# Master_System_Converter_Plus.net
KiCad netlist of a schematic drawn in EasyEDA
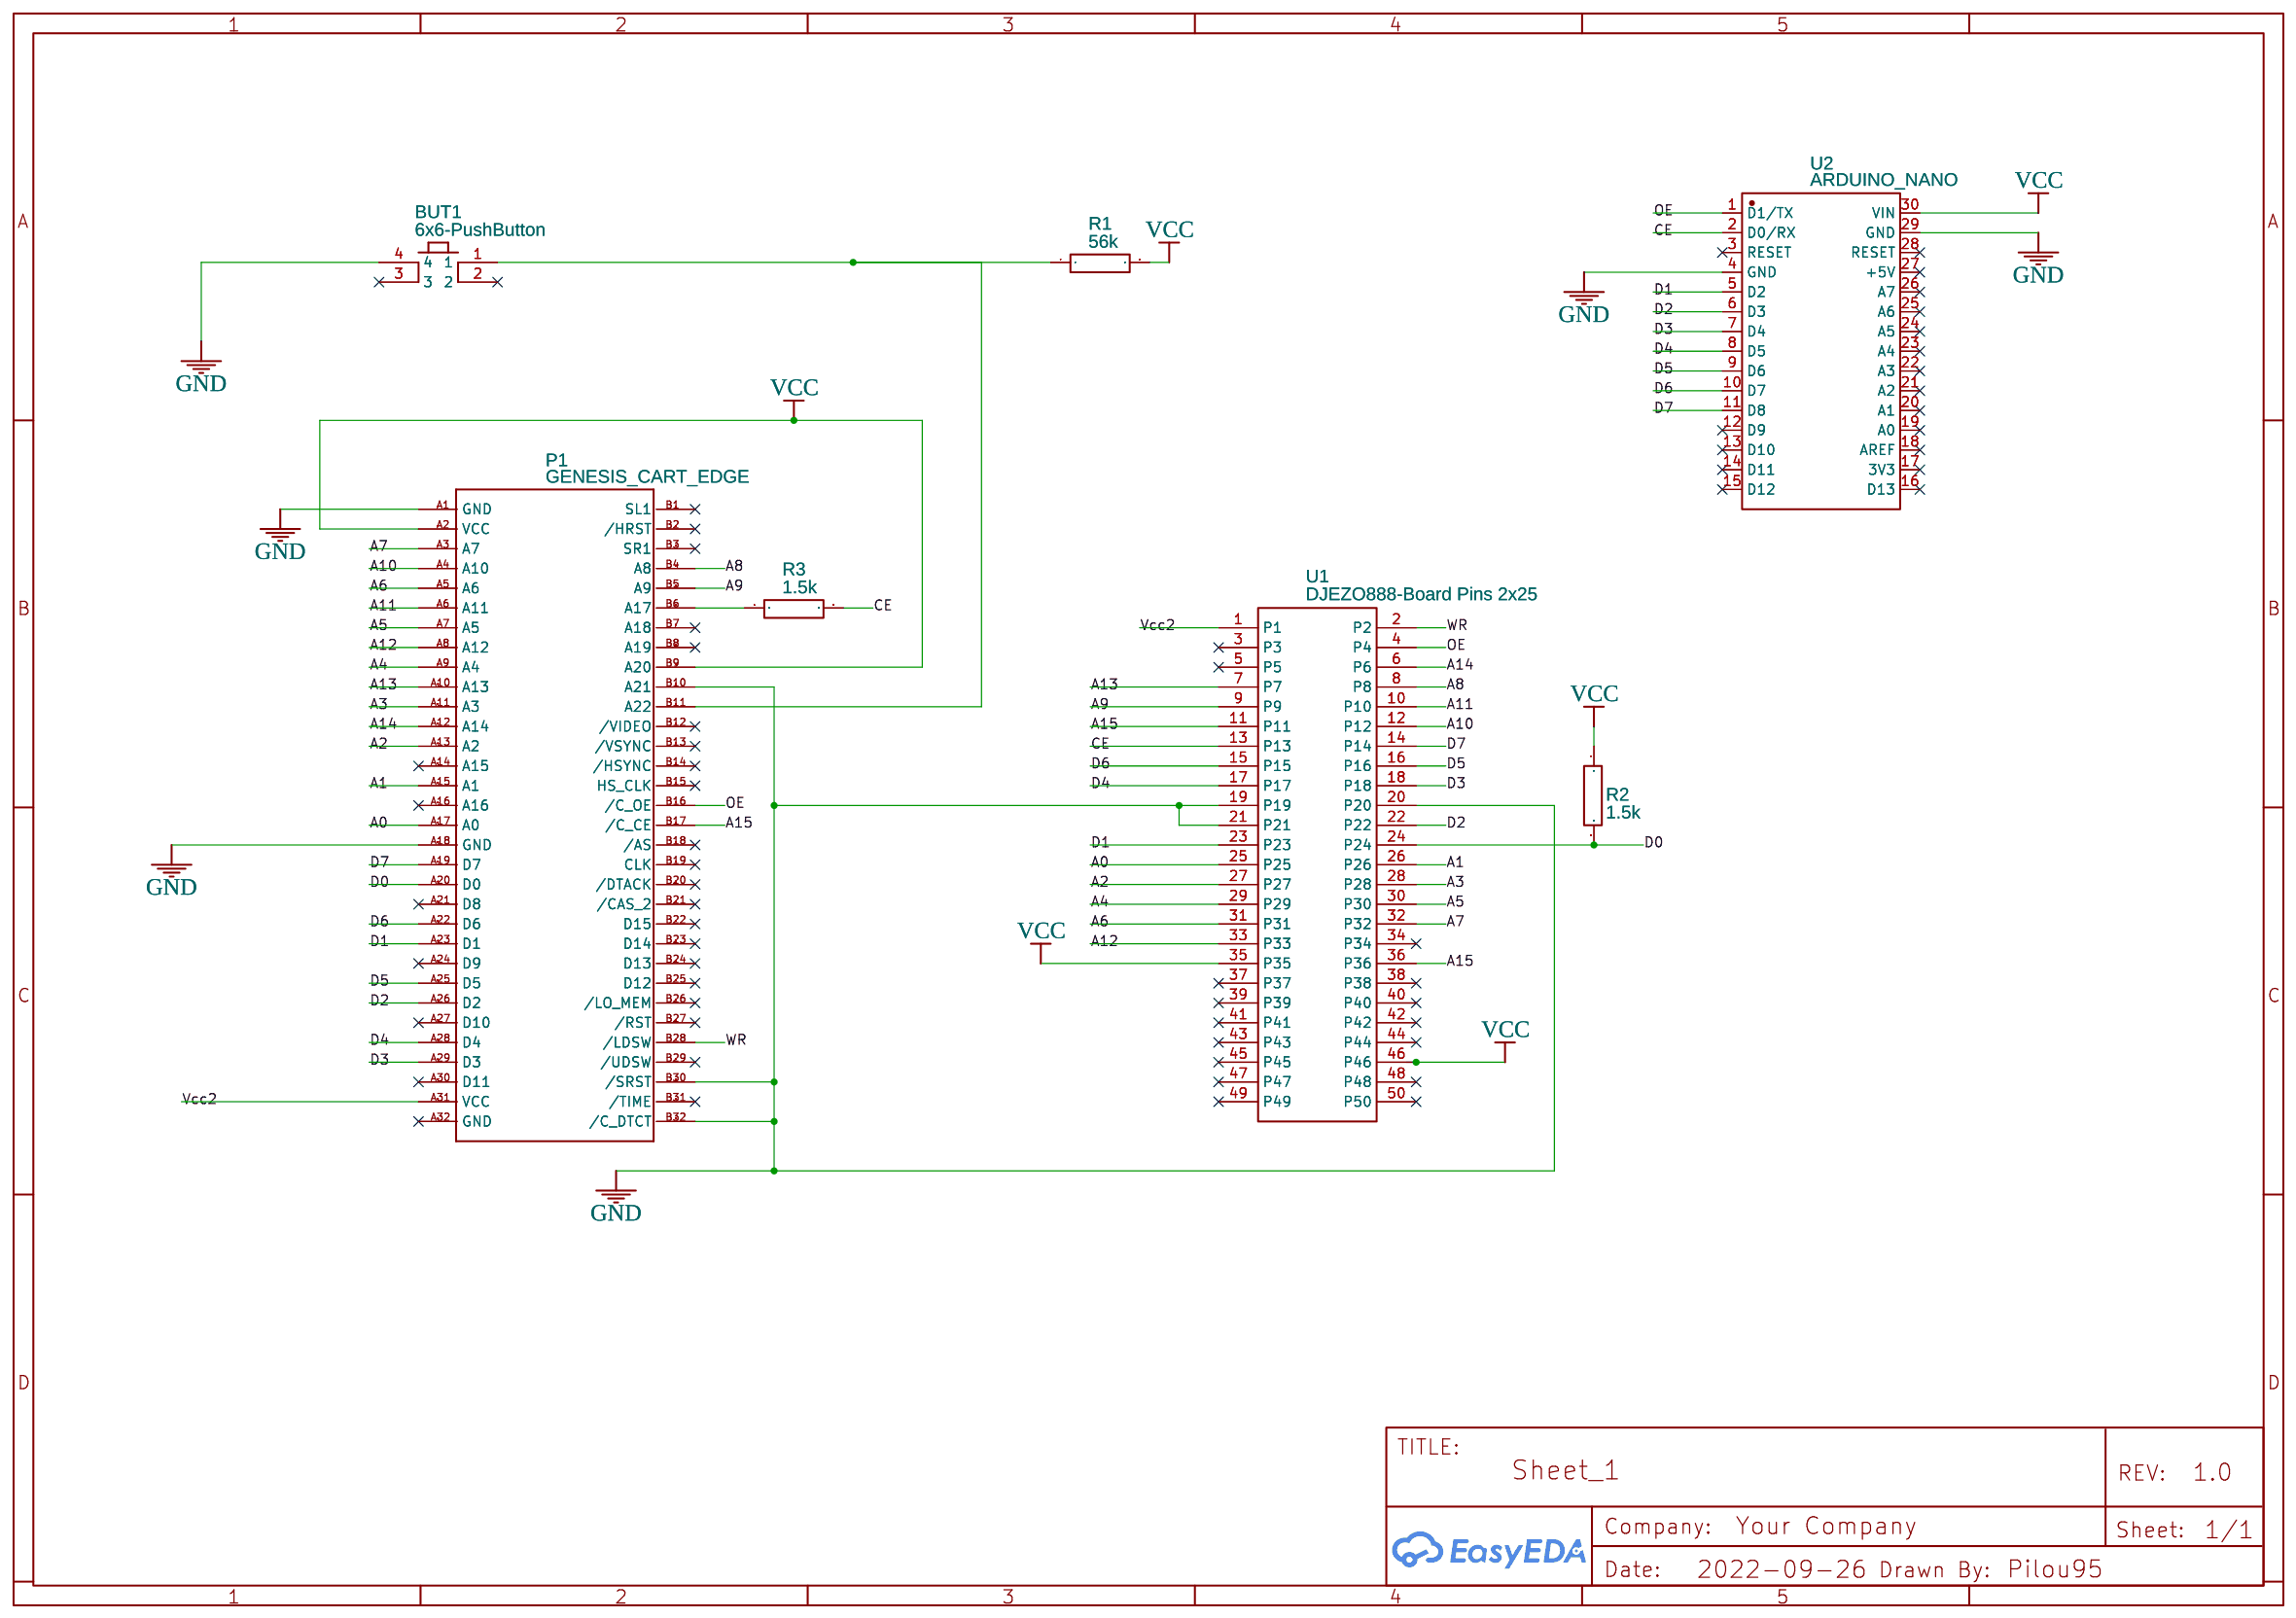
[diagram p0: schematic sheet]

(export (version "E")
  (design (tool "Eeschema 10.0.6"))
  (components
    (comp (ref "BUT1") (value "6x6-PushButton") (libsource (lib "") (part "6x6-PushButton")))
    (comp (ref "P1") (value "GENESIS_CART_EDGE") (libsource (lib "") (part "GENESIS_CART_EDGE")))
    (comp (ref "R1") (value "56k") (libsource (lib "") (part "resistance_1")))
    (comp (ref "R2") (value "1.5k") (libsource (lib "") (part "resistance")))
    (comp (ref "R3") (value "1.5k") (libsource (lib "") (part "resistance_1")))
    (comp (ref "U1")
      (value "DJEZO888-Board Pins 2x25")
      (libsource (lib "") (part "DJEZO888-Board Pins 2x25"))
    )
    (comp (ref "U2")
      (value "ARDUINO_NANO")
      (fields (field (name "BOM_Supplier Part") "C9900017879"))
      (libsource (lib "") (part "ARDUINO_NANO"))
    )
  )
  (nets
    (net (code "1") (name "/A0") (class "Default")
      (node (ref "P1") (pin "A17") (pinfunction "A0_A17") (pintype "bidirectional"))
      (node (ref "U1") (pin "25") (pinfunction "P25_25") (pintype "unspecified"))
    )
    (net (code "2") (name "/A1") (class "Default")
      (node (ref "P1") (pin "A15") (pinfunction "A1_A15") (pintype "bidirectional"))
      (node (ref "U1") (pin "26") (pinfunction "P26_26") (pintype "unspecified"))
    )
    (net (code "3") (name "/A2") (class "Default")
      (node (ref "P1") (pin "A13") (pinfunction "A2_A13") (pintype "bidirectional"))
      (node (ref "U1") (pin "27") (pinfunction "P27_27") (pintype "unspecified"))
    )
    (net (code "4") (name "/A3") (class "Default")
      (node (ref "P1") (pin "A11") (pinfunction "A3_A11") (pintype "bidirectional"))
      (node (ref "U1") (pin "28") (pinfunction "P28_28") (pintype "unspecified"))
    )
    (net (code "5") (name "/A4") (class "Default")
      (node (ref "P1") (pin "A9") (pinfunction "A4_A9") (pintype "bidirectional"))
      (node (ref "U1") (pin "29") (pinfunction "P29_29") (pintype "unspecified"))
    )
    (net (code "6") (name "/A5") (class "Default")
      (node (ref "P1") (pin "A7") (pinfunction "A5_A7") (pintype "bidirectional"))
      (node (ref "U1") (pin "30") (pinfunction "P30_30") (pintype "unspecified"))
    )
    (net (code "7") (name "/A6") (class "Default")
      (node (ref "P1") (pin "A5") (pinfunction "A6_A5") (pintype "bidirectional"))
      (node (ref "U1") (pin "31") (pinfunction "P31_31") (pintype "unspecified"))
    )
    (net (code "8") (name "/A7") (class "Default")
      (node (ref "P1") (pin "A3") (pinfunction "A7_A3") (pintype "bidirectional"))
      (node (ref "U1") (pin "32") (pinfunction "P32_32") (pintype "unspecified"))
    )
    (net (code "9") (name "/A8") (class "Default")
      (node (ref "P1") (pin "B4") (pinfunction "A8_B4") (pintype "bidirectional"))
      (node (ref "U1") (pin "8") (pinfunction "P8_8") (pintype "unspecified"))
    )
    (net (code "10") (name "/A9") (class "Default")
      (node (ref "P1") (pin "B5") (pinfunction "A9_B5") (pintype "bidirectional"))
      (node (ref "U1") (pin "9") (pinfunction "P9_9") (pintype "unspecified"))
    )
    (net (code "11") (name "/A10") (class "Default")
      (node (ref "P1") (pin "A4") (pinfunction "A10_A4") (pintype "bidirectional"))
      (node (ref "U1") (pin "12") (pinfunction "P12_12") (pintype "unspecified"))
    )
    (net (code "12") (name "/A11") (class "Default")
      (node (ref "P1") (pin "A6") (pinfunction "A11_A6") (pintype "bidirectional"))
      (node (ref "U1") (pin "10") (pinfunction "P10_10") (pintype "unspecified"))
    )
    (net (code "13") (name "/A12") (class "Default")
      (node (ref "P1") (pin "A8") (pinfunction "A12_A8") (pintype "bidirectional"))
      (node (ref "U1") (pin "33") (pinfunction "P33_33") (pintype "unspecified"))
    )
    (net (code "14") (name "/A13") (class "Default")
      (node (ref "P1") (pin "A10") (pinfunction "A13_A10") (pintype "bidirectional"))
      (node (ref "U1") (pin "7") (pinfunction "P7_7") (pintype "unspecified"))
    )
    (net (code "15") (name "/A14") (class "Default")
      (node (ref "P1") (pin "A12") (pinfunction "A14_A12") (pintype "bidirectional"))
      (node (ref "U1") (pin "6") (pinfunction "P6_6") (pintype "unspecified"))
    )
    (net (code "16") (name "/A15") (class "Default")
      (node (ref "P1") (pin "B17") (pinfunction "/C_CE_B17") (pintype "bidirectional"))
      (node (ref "U1") (pin "11") (pinfunction "P11_11") (pintype "unspecified"))
      (node (ref "U1") (pin "36") (pinfunction "P36_36") (pintype "unspecified"))
    )
    (net (code "17") (name "/CE") (class "Default")
      (node (ref "R3") (pin "2") (pinfunction "2_2") (pintype "unspecified"))
      (node (ref "U1") (pin "13") (pinfunction "P13_13") (pintype "unspecified"))
      (node (ref "U2") (pin "2") (pinfunction "D0/RX_2") (pintype "unspecified"))
    )
    (net (code "18") (name "/D0") (class "Default")
      (node (ref "P1") (pin "A20") (pinfunction "D0_A20") (pintype "bidirectional"))
      (node (ref "R2") (pin "2") (pinfunction "2_2") (pintype "unspecified"))
      (node (ref "U1") (pin "24") (pinfunction "P24_24") (pintype "unspecified"))
    )
    (net (code "19") (name "/D1") (class "Default")
      (node (ref "P1") (pin "A23") (pinfunction "D1_A23") (pintype "bidirectional"))
      (node (ref "U1") (pin "23") (pinfunction "P23_23") (pintype "unspecified"))
      (node (ref "U2") (pin "5") (pinfunction "D2_5") (pintype "unspecified"))
    )
    (net (code "20") (name "/D2") (class "Default")
      (node (ref "P1") (pin "A26") (pinfunction "D2_A26") (pintype "bidirectional"))
      (node (ref "U1") (pin "22") (pinfunction "P22_22") (pintype "unspecified"))
      (node (ref "U2") (pin "6") (pinfunction "D3_6") (pintype "unspecified"))
    )
    (net (code "21") (name "/D3") (class "Default")
      (node (ref "P1") (pin "A29") (pinfunction "D3_A29") (pintype "bidirectional"))
      (node (ref "U1") (pin "18") (pinfunction "P18_18") (pintype "unspecified"))
      (node (ref "U2") (pin "7") (pinfunction "D4_7") (pintype "unspecified"))
    )
    (net (code "22") (name "/D4") (class "Default")
      (node (ref "P1") (pin "A28") (pinfunction "D4_A28") (pintype "bidirectional"))
      (node (ref "U1") (pin "17") (pinfunction "P17_17") (pintype "unspecified"))
      (node (ref "U2") (pin "8") (pinfunction "D5_8") (pintype "unspecified"))
    )
    (net (code "23") (name "/D5") (class "Default")
      (node (ref "P1") (pin "A25") (pinfunction "D5_A25") (pintype "bidirectional"))
      (node (ref "U1") (pin "16") (pinfunction "P16_16") (pintype "unspecified"))
      (node (ref "U2") (pin "9") (pinfunction "D6_9") (pintype "unspecified"))
    )
    (net (code "24") (name "/D6") (class "Default")
      (node (ref "P1") (pin "A22") (pinfunction "D6_A22") (pintype "bidirectional"))
      (node (ref "U1") (pin "15") (pinfunction "P15_15") (pintype "unspecified"))
      (node (ref "U2") (pin "10") (pinfunction "D7_10") (pintype "unspecified"))
    )
    (net (code "25") (name "/D7") (class "Default")
      (node (ref "P1") (pin "A19") (pinfunction "D7_A19") (pintype "bidirectional"))
      (node (ref "U1") (pin "14") (pinfunction "P14_14") (pintype "unspecified"))
      (node (ref "U2") (pin "11") (pinfunction "D8_11") (pintype "unspecified"))
    )
    (net (code "26") (name "/OE") (class "Default")
      (node (ref "P1") (pin "B16") (pinfunction "/C_OE_B16") (pintype "bidirectional"))
      (node (ref "U1") (pin "4") (pinfunction "P4_4") (pintype "unspecified"))
      (node (ref "U2") (pin "1") (pinfunction "D1/TX_1") (pintype "unspecified"))
    )
    (net (code "27") (name "/Vcc2") (class "Default")
      (node (ref "P1") (pin "A31") (pinfunction "VCC_A31") (pintype "bidirectional"))
      (node (ref "U1") (pin "1") (pinfunction "P1_1") (pintype "unspecified"))
    )
    (net (code "28") (name "/WR") (class "Default")
      (node (ref "P1") (pin "B28") (pinfunction "/LDSW_B28") (pintype "bidirectional"))
      (node (ref "U1") (pin "2") (pinfunction "P2_2") (pintype "unspecified"))
    )
    (net (code "29") (name "GND") (class "Default")
      (node (ref "BUT1") (pin "4") (pinfunction "4_4") (pintype "unspecified"))
      (node (ref "P1") (pin "A1") (pinfunction "GND_A1") (pintype "bidirectional"))
      (node (ref "P1") (pin "A18") (pinfunction "GND_A18") (pintype "bidirectional"))
      (node (ref "P1") (pin "B10") (pinfunction "A21_B10") (pintype "bidirectional"))
      (node (ref "P1") (pin "B30") (pinfunction "/SRST_B30") (pintype "bidirectional"))
      (node (ref "P1") (pin "B32") (pinfunction "/C_DTCT_B32") (pintype "bidirectional"))
      (node (ref "U1") (pin "19") (pinfunction "P19_19") (pintype "unspecified"))
      (node (ref "U1") (pin "20") (pinfunction "P20_20") (pintype "unspecified"))
      (node (ref "U1") (pin "21") (pinfunction "P21_21") (pintype "unspecified"))
      (node (ref "U2") (pin "29") (pinfunction "GND_29") (pintype "unspecified"))
      (node (ref "U2") (pin "4") (pinfunction "GND_4") (pintype "unspecified"))
    )
    (net (code "30") (name "Net-(P1-A17)") (class "Default")
      (node (ref "P1") (pin "B6") (pinfunction "A17_B6") (pintype "bidirectional"))
      (node (ref "R3") (pin "1") (pinfunction "1_1") (pintype "unspecified"))
    )
    (net (code "31") (name "Net-(P1-A22)") (class "Default")
      (node (ref "BUT1") (pin "1") (pinfunction "1_1") (pintype "unspecified"))
      (node (ref "P1") (pin "B11") (pinfunction "A22_B11") (pintype "bidirectional"))
      (node (ref "R1") (pin "1") (pinfunction "1_1") (pintype "unspecified"))
    )
    (net (code "32") (name "VCC") (class "Default")
      (node (ref "P1") (pin "A2") (pinfunction "VCC_A2") (pintype "bidirectional"))
      (node (ref "P1") (pin "B9") (pinfunction "A20_B9") (pintype "bidirectional"))
      (node (ref "R1") (pin "2") (pinfunction "2_2") (pintype "unspecified"))
      (node (ref "R2") (pin "1") (pinfunction "1_1") (pintype "unspecified"))
      (node (ref "U1") (pin "35") (pinfunction "P35_35") (pintype "unspecified"))
      (node (ref "U1") (pin "46") (pinfunction "P46_46") (pintype "unspecified"))
      (node (ref "U2") (pin "30") (pinfunction "VIN_30") (pintype "unspecified"))
    )
    (net (code "33") (name "unconnected-(BUT1-Pad2)") (class "Default")
      (node (ref "BUT1") (pin "2") (pinfunction "2_2") (pintype "unspecified+no_connect"))
    )
    (net (code "34") (name "unconnected-(BUT1-Pad3)") (class "Default")
      (node (ref "BUT1") (pin "3") (pinfunction "3_3") (pintype "unspecified+no_connect"))
    )
    (net (code "35") (name "unconnected-(P1-A15-PadA14)") (class "Default")
      (node (ref "P1") (pin "A14") (pinfunction "A15_A14") (pintype "bidirectional+no_connect"))
    )
    (net (code "36") (name "unconnected-(P1-A18-PadB7)") (class "Default")
      (node (ref "P1") (pin "B7") (pinfunction "A18_B7") (pintype "bidirectional+no_connect"))
    )
    (net (code "37") (name "unconnected-(P1-A19-PadB8)") (class "Default")
      (node (ref "P1") (pin "B8") (pinfunction "A19_B8") (pintype "bidirectional+no_connect"))
    )
    (net (code "38") (name "unconnected-(P1-CLK-PadB19)") (class "Default")
      (node (ref "P1") (pin "B19") (pinfunction "CLK_B19") (pintype "bidirectional+no_connect"))
    )
    (net (code "39") (name "unconnected-(P1-D8-PadA21)") (class "Default")
      (node (ref "P1") (pin "A21") (pinfunction "D8_A21") (pintype "bidirectional+no_connect"))
    )
    (net (code "40") (name "unconnected-(P1-D9-PadA24)") (class "Default")
      (node (ref "P1") (pin "A24") (pinfunction "D9_A24") (pintype "bidirectional+no_connect"))
    )
    (net (code "41") (name "unconnected-(P1-D10-PadA27)") (class "Default")
      (node (ref "P1") (pin "A27") (pinfunction "D10_A27") (pintype "bidirectional+no_connect"))
    )
    (net (code "42") (name "unconnected-(P1-D11-PadA30)") (class "Default")
      (node (ref "P1") (pin "A30") (pinfunction "D11_A30") (pintype "bidirectional+no_connect"))
    )
    (net (code "43") (name "unconnected-(P1-D12-PadB25)") (class "Default")
      (node (ref "P1") (pin "B25") (pinfunction "D12_B25") (pintype "bidirectional+no_connect"))
    )
    (net (code "44") (name "unconnected-(P1-D13-PadB24)") (class "Default")
      (node (ref "P1") (pin "B24") (pinfunction "D13_B24") (pintype "bidirectional+no_connect"))
    )
    (net (code "45") (name "unconnected-(P1-D14-PadB23)") (class "Default")
      (node (ref "P1") (pin "B23") (pinfunction "D14_B23") (pintype "bidirectional+no_connect"))
    )
    (net (code "46") (name "unconnected-(P1-D15-PadB22)") (class "Default")
      (node (ref "P1") (pin "B22") (pinfunction "D15_B22") (pintype "bidirectional+no_connect"))
    )
    (net (code "47") (name "unconnected-(P1-GND-PadA32)") (class "Default")
      (node (ref "P1") (pin "A32") (pinfunction "GND_A32") (pintype "bidirectional+no_connect"))
    )
    (net (code "48") (name "unconnected-(P1-HS_CLK-PadB15)") (class "Default")
      (node (ref "P1") (pin "B15") (pinfunction "HS_CLK_B15") (pintype "bidirectional+no_connect"))
    )
    (net (code "49") (name "unconnected-(P1-PadA16)") (class "Default")
      (node (ref "P1") (pin "A16") (pinfunction "A16_A16") (pintype "bidirectional+no_connect"))
    )
    (net (code "50") (name "unconnected-(P1-SL1-PadB1)") (class "Default")
      (node (ref "P1") (pin "B1") (pinfunction "SL1_B1") (pintype "bidirectional+no_connect"))
    )
    (net (code "51") (name "unconnected-(P1-SR1-PadB3)") (class "Default")
      (node (ref "P1") (pin "B3") (pinfunction "SR1_B3") (pintype "bidirectional+no_connect"))
    )
    (net (code "52") (name "unconnected-(P1-{slash}AS-PadB18)") (class "Default")
      (node (ref "P1") (pin "B18") (pinfunction "/AS_B18") (pintype "bidirectional+no_connect"))
    )
    (net (code "53") (name "unconnected-(P1-{slash}CAS_2-PadB21)") (class "Default")
      (node (ref "P1") (pin "B21") (pinfunction "/CAS_2_B21") (pintype "bidirectional+no_connect"))
    )
    (net (code "54") (name "unconnected-(P1-{slash}DTACK-PadB20)") (class "Default")
      (node (ref "P1") (pin "B20") (pinfunction "/DTACK_B20") (pintype "bidirectional+no_connect"))
    )
    (net (code "55") (name "unconnected-(P1-{slash}HRST-PadB2)") (class "Default")
      (node (ref "P1") (pin "B2") (pinfunction "/HRST_B2") (pintype "bidirectional+no_connect"))
    )
    (net (code "56") (name "unconnected-(P1-{slash}HSYNC-PadB14)") (class "Default")
      (node (ref "P1") (pin "B14") (pinfunction "/HSYNC_B14") (pintype "bidirectional+no_connect"))
    )
    (net (code "57") (name "unconnected-(P1-{slash}LO_MEM-PadB26)") (class "Default")
      (node (ref "P1") (pin "B26") (pinfunction "/LO_MEM_B26") (pintype "bidirectional+no_connect"))
    )
    (net (code "58") (name "unconnected-(P1-{slash}RST-PadB27)") (class "Default")
      (node (ref "P1") (pin "B27") (pinfunction "/RST_B27") (pintype "bidirectional+no_connect"))
    )
    (net (code "59") (name "unconnected-(P1-{slash}TIME-PadB31)") (class "Default")
      (node (ref "P1") (pin "B31") (pinfunction "/TIME_B31") (pintype "bidirectional+no_connect"))
    )
    (net (code "60") (name "unconnected-(P1-{slash}UDSW-PadB29)") (class "Default")
      (node (ref "P1") (pin "B29") (pinfunction "/UDSW_B29") (pintype "bidirectional+no_connect"))
    )
    (net (code "61") (name "unconnected-(P1-{slash}VIDEO-PadB12)") (class "Default")
      (node (ref "P1") (pin "B12") (pinfunction "/VIDEO_B12") (pintype "bidirectional+no_connect"))
    )
    (net (code "62") (name "unconnected-(P1-{slash}VSYNC-PadB13)") (class "Default")
      (node (ref "P1") (pin "B13") (pinfunction "/VSYNC_B13") (pintype "bidirectional+no_connect"))
    )
    (net (code "63") (name "unconnected-(U1-P3-Pad3)") (class "Default")
      (node (ref "U1") (pin "3") (pinfunction "P3_3") (pintype "unspecified+no_connect"))
    )
    (net (code "64") (name "unconnected-(U1-P5-Pad5)") (class "Default")
      (node (ref "U1") (pin "5") (pinfunction "P5_5") (pintype "unspecified+no_connect"))
    )
    (net (code "65") (name "unconnected-(U1-P34-Pad34)") (class "Default")
      (node (ref "U1") (pin "34") (pinfunction "P34_34") (pintype "unspecified+no_connect"))
    )
    (net (code "66") (name "unconnected-(U1-P37-Pad37)") (class "Default")
      (node (ref "U1") (pin "37") (pinfunction "P37_37") (pintype "unspecified+no_connect"))
    )
    (net (code "67") (name "unconnected-(U1-P38-Pad38)") (class "Default")
      (node (ref "U1") (pin "38") (pinfunction "P38_38") (pintype "unspecified+no_connect"))
    )
    (net (code "68") (name "unconnected-(U1-P39-Pad39)") (class "Default")
      (node (ref "U1") (pin "39") (pinfunction "P39_39") (pintype "unspecified+no_connect"))
    )
    (net (code "69") (name "unconnected-(U1-P40-Pad40)") (class "Default")
      (node (ref "U1") (pin "40") (pinfunction "P40_40") (pintype "unspecified+no_connect"))
    )
    (net (code "70") (name "unconnected-(U1-P41-Pad41)") (class "Default")
      (node (ref "U1") (pin "41") (pinfunction "P41_41") (pintype "unspecified+no_connect"))
    )
    (net (code "71") (name "unconnected-(U1-P42-Pad42)") (class "Default")
      (node (ref "U1") (pin "42") (pinfunction "P42_42") (pintype "unspecified+no_connect"))
    )
    (net (code "72") (name "unconnected-(U1-P43-Pad43)") (class "Default")
      (node (ref "U1") (pin "43") (pinfunction "P43_43") (pintype "unspecified+no_connect"))
    )
    (net (code "73") (name "unconnected-(U1-P44-Pad44)") (class "Default")
      (node (ref "U1") (pin "44") (pinfunction "P44_44") (pintype "unspecified+no_connect"))
    )
    (net (code "74") (name "unconnected-(U1-P45-Pad45)") (class "Default")
      (node (ref "U1") (pin "45") (pinfunction "P45_45") (pintype "unspecified+no_connect"))
    )
    (net (code "75") (name "unconnected-(U1-P47-Pad47)") (class "Default")
      (node (ref "U1") (pin "47") (pinfunction "P47_47") (pintype "unspecified+no_connect"))
    )
    (net (code "76") (name "unconnected-(U1-P48-Pad48)") (class "Default")
      (node (ref "U1") (pin "48") (pinfunction "P48_48") (pintype "unspecified+no_connect"))
    )
    (net (code "77") (name "unconnected-(U1-P49-Pad49)") (class "Default")
      (node (ref "U1") (pin "49") (pinfunction "P49_49") (pintype "unspecified+no_connect"))
    )
    (net (code "78") (name "unconnected-(U1-P50-Pad50)") (class "Default")
      (node (ref "U1") (pin "50") (pinfunction "P50_50") (pintype "unspecified+no_connect"))
    )
    (net (code "79") (name "unconnected-(U2-+5V-Pad27)") (class "Default")
      (node (ref "U2") (pin "27") (pinfunction "+5V_27") (pintype "unspecified+no_connect"))
    )
    (net (code "80") (name "unconnected-(U2-3V3-Pad17)") (class "Default")
      (node (ref "U2") (pin "17") (pinfunction "3V3_17") (pintype "unspecified+no_connect"))
    )
    (net (code "81") (name "unconnected-(U2-A0-Pad19)") (class "Default")
      (node (ref "U2") (pin "19") (pinfunction "A0_19") (pintype "unspecified+no_connect"))
    )
    (net (code "82") (name "unconnected-(U2-A1-Pad20)") (class "Default")
      (node (ref "U2") (pin "20") (pinfunction "A1_20") (pintype "unspecified+no_connect"))
    )
    (net (code "83") (name "unconnected-(U2-A2-Pad21)") (class "Default")
      (node (ref "U2") (pin "21") (pinfunction "A2_21") (pintype "unspecified+no_connect"))
    )
    (net (code "84") (name "unconnected-(U2-A3-Pad22)") (class "Default")
      (node (ref "U2") (pin "22") (pinfunction "A3_22") (pintype "unspecified+no_connect"))
    )
    (net (code "85") (name "unconnected-(U2-A4-Pad23)") (class "Default")
      (node (ref "U2") (pin "23") (pinfunction "A4_23") (pintype "unspecified+no_connect"))
    )
    (net (code "86") (name "unconnected-(U2-A5-Pad24)") (class "Default")
      (node (ref "U2") (pin "24") (pinfunction "A5_24") (pintype "unspecified+no_connect"))
    )
    (net (code "87") (name "unconnected-(U2-A6-Pad25)") (class "Default")
      (node (ref "U2") (pin "25") (pinfunction "A6_25") (pintype "unspecified+no_connect"))
    )
    (net (code "88") (name "unconnected-(U2-A7-Pad26)") (class "Default")
      (node (ref "U2") (pin "26") (pinfunction "A7_26") (pintype "unspecified+no_connect"))
    )
    (net (code "89") (name "unconnected-(U2-AREF-Pad18)") (class "Default")
      (node (ref "U2") (pin "18") (pinfunction "AREF_18") (pintype "unspecified+no_connect"))
    )
    (net (code "90") (name "unconnected-(U2-D9-Pad12)") (class "Default")
      (node (ref "U2") (pin "12") (pinfunction "D9_12") (pintype "unspecified+no_connect"))
    )
    (net (code "91") (name "unconnected-(U2-D10-Pad13)") (class "Default")
      (node (ref "U2") (pin "13") (pinfunction "D10_13") (pintype "unspecified+no_connect"))
    )
    (net (code "92") (name "unconnected-(U2-D11-Pad14)") (class "Default")
      (node (ref "U2") (pin "14") (pinfunction "D11_14") (pintype "unspecified+no_connect"))
    )
    (net (code "93") (name "unconnected-(U2-D12-Pad15)") (class "Default")
      (node (ref "U2") (pin "15") (pinfunction "D12_15") (pintype "unspecified+no_connect"))
    )
    (net (code "94") (name "unconnected-(U2-D13-Pad16)") (class "Default")
      (node (ref "U2") (pin "16") (pinfunction "D13_16") (pintype "unspecified+no_connect"))
    )
    (net (code "95") (name "unconnected-(U2-RESET-Pad3)") (class "Default")
      (node (ref "U2") (pin "3") (pinfunction "RESET_3") (pintype "unspecified+no_connect"))
    )
    (net (code "96") (name "unconnected-(U2-RESET-Pad28)") (class "Default")
      (node (ref "U2") (pin "28") (pinfunction "RESET_28") (pintype "unspecified+no_connect"))
    )
  )
)
